# asset-tracker-v003.net
KiCad netlist of a schematic drawn in EAGLE
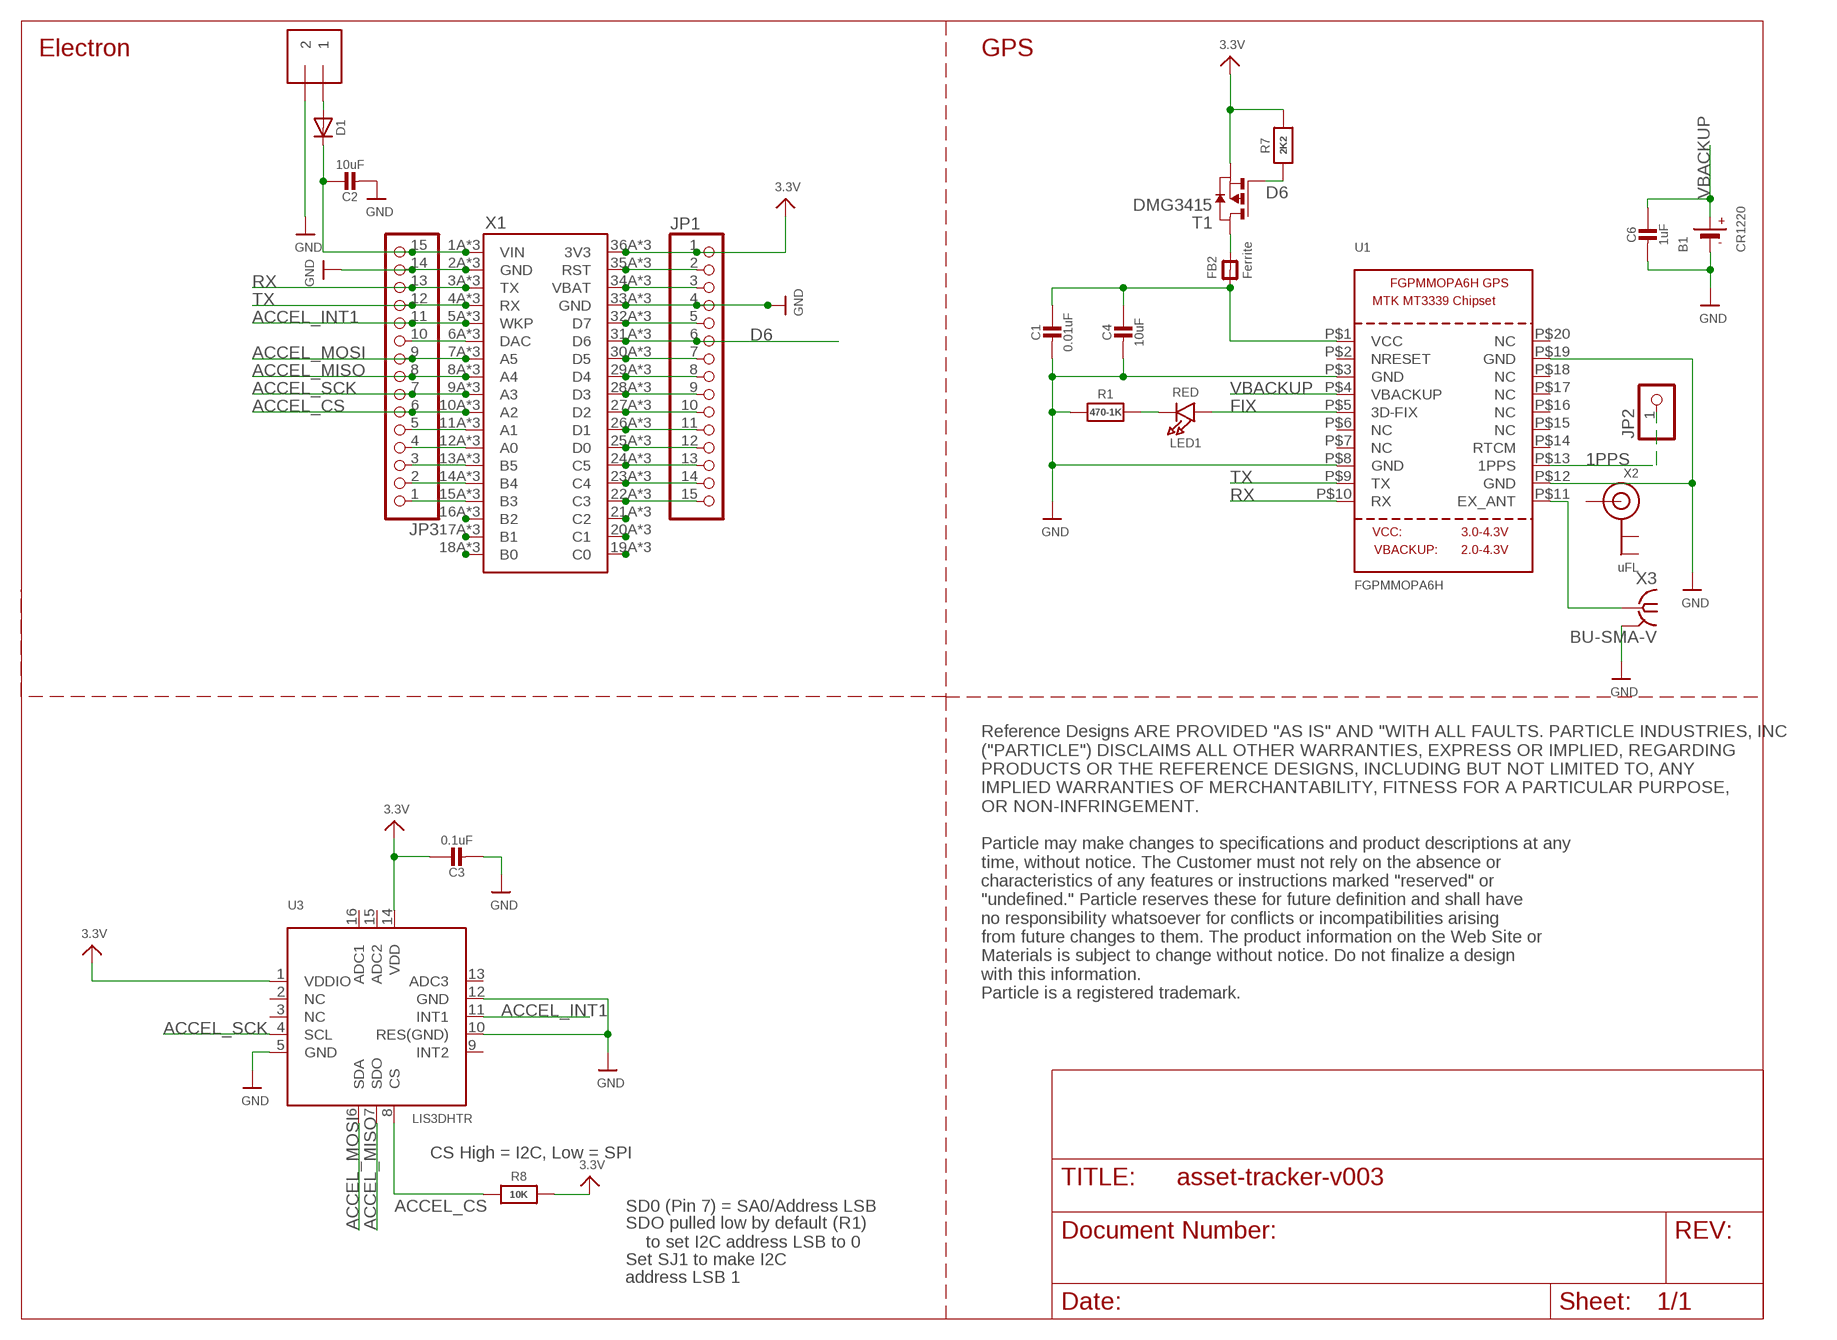
[diagram p0: schematic, sheet 1]

(export (version "E")
  (design (tool "Eeschema 10.0.6"))
  (components
    (comp (ref "B1")
      (value "CR1220")
      (footprint "eagle-import:CR1220")
      (libsource (lib "eagle-import") (part "BATTERYCR1220_SMT"))
    )
    (comp (ref "C1")
      (value "0.01uF")
      (footprint "eagle-import:0805-NO@1")
      (libsource (lib "eagle-import") (part "CAP_CERAMIC0805-NOOUTLINE"))
    )
    (comp (ref "C2")
      (value "10uF")
      (footprint "eagle-import:0805-NO@1")
      (libsource (lib "eagle-import") (part "CAP_CERAMIC0805-NOOUTLINE"))
    )
    (comp (ref "C3")
      (value "0.1uF")
      (footprint "eagle-import:0805_10MGAP")
      (libsource (lib "eagle-import") (part "CAP_CERAMIC0805_10MGAP"))
    )
    (comp (ref "C4")
      (value "10uF")
      (footprint "eagle-import:0805-NO@1")
      (libsource (lib "eagle-import") (part "CAP_CERAMIC0805-NOOUTLINE"))
    )
    (comp (ref "C6")
      (value "1uF")
      (footprint "eagle-import:0805-NO@1")
      (libsource (lib "eagle-import") (part "CAP_CERAMIC0805-NOOUTLINE"))
    )
    (comp (ref "D1")
      (value "DIODESMA")
      (footprint "eagle-import:SMADIODE")
      (libsource (lib "eagle-import") (part "DIODESMA"))
    )
    (comp (ref "FB2")
      (value "Ferrite")
      (footprint "eagle-import:0805-NO@1")
      (libsource (lib "eagle-import") (part "FERRITE-0805NO"))
    )
    (comp (ref "J1")
      (value "1X2-3.5MM")
      (footprint "eagle-import:1X2-3.5MM")
      (libsource (lib "eagle-import") (part "1X2-3.5MM"))
    )
    (comp (ref "JP1")
      (value "HEADER-1X15")
      (footprint "eagle-import:1X15_ROUND_70")
      (libsource (lib "eagle-import") (part "HEADER-1X15"))
    )
    (comp (ref "JP2")
      (value "HEADER-1X1ROUND")
      (footprint "eagle-import:1X01_ROUND")
      (libsource (lib "eagle-import") (part "HEADER-1X1ROUND"))
    )
    (comp (ref "JP3")
      (value "HEADER-1X15")
      (footprint "eagle-import:1X15_ROUND_70")
      (libsource (lib "eagle-import") (part "HEADER-1X15"))
    )
    (comp (ref "LED1")
      (value "RED")
      (footprint "eagle-import:CHIPLED_0805_NOOUTLINE")
      (libsource (lib "eagle-import") (part "LED0805_NOOUTLINE"))
    )
    (comp (ref "R1")
      (value "470-1K")
      (footprint "eagle-import:0805-NO")
      (libsource (lib "eagle-import") (part "RESISTOR0805_NOOUTLINE"))
    )
    (comp (ref "R7")
      (value "2K2")
      (footprint "eagle-import:0805-NO")
      (libsource (lib "eagle-import") (part "RESISTOR0805_NOOUTLINE"))
    )
    (comp (ref "R8")
      (value "10K")
      (footprint "eagle-import:0805-NO")
      (libsource (lib "eagle-import") (part "RESISTOR0805_NOOUTLINE"))
    )
    (comp (ref "T1")
      (value "DMG3415")
      (footprint "eagle-import:SOT-23")
      (libsource (lib "eagle-import") (part "PMOSSOT23"))
    )
    (comp (ref "U1")
      (value "FGPMMOPA6H")
      (footprint "eagle-import:FGPMMOPA6H")
      (libsource (lib "eagle-import") (part "GPS_FGPMMOPA6H"))
    )
    (comp (ref "U3")
      (value "LIS3DHTR")
      (footprint "eagle-import:LGA16_3X3MM")
      (libsource (lib "eagle-import") (part "ACCEL_LIS3DHTR"))
    )
    (comp (ref "X1")
      (value "ELECTRON")
      (footprint "eagle-import:ELECTRON_SMT")
      (libsource (lib "eagle-import") (part "ELECTRON_SMT"))
    )
    (comp (ref "X2")
      (value "uFL")
      (footprint "eagle-import:U.FL")
      (libsource (lib "eagle-import") (part "ANTENNA_U.FL"))
    )
    (comp (ref "X3")
      (value "BU-SMA-V")
      (footprint "eagle-import:BU-SMA-V")
      (libsource (lib "eagle-import") (part "BU-SMA-V"))
    )
  )
  (nets
    (net (code "1") (name "/1PPS") (class "Default")
      (node (ref "JP2") (pin "1") (pinfunction "1_1") (pintype "passive"))
      (node (ref "U1") (pin "P$13") (pinfunction "1PPS_P$13") (pintype "bidirectional"))
    )
    (net (code "2") (name "/ACCEL_CS") (class "Default")
      (node (ref "JP3") (pin "6") (pinfunction "6_6") (pintype "passive"))
      (node (ref "R8") (pin "1") (pinfunction "1_1") (pintype "passive"))
      (node (ref "U3") (pin "8") (pinfunction "CS_8") (pintype "input"))
      (node (ref "X1") (pin "10A") (pinfunction "A2_10A") (pintype "bidirectional"))
      (node (ref "X1") (pin "10B") (pinfunction "A2_10B") (pintype "bidirectional"))
      (node (ref "X1") (pin "10C") (pinfunction "A2_10C") (pintype "bidirectional"))
    )
    (net (code "3") (name "/ACCEL_INT1") (class "Default")
      (node (ref "JP3") (pin "11") (pinfunction "11_11") (pintype "passive"))
      (node (ref "U3") (pin "11") (pinfunction "INT1_11") (pintype "output"))
      (node (ref "X1") (pin "5A") (pinfunction "WKP_5A") (pintype "bidirectional"))
      (node (ref "X1") (pin "5B") (pinfunction "WKP_5B") (pintype "bidirectional"))
      (node (ref "X1") (pin "5C") (pinfunction "WKP_5C") (pintype "bidirectional"))
    )
    (net (code "4") (name "/ACCEL_MISO") (class "Default")
      (node (ref "JP3") (pin "8") (pinfunction "8_8") (pintype "passive"))
      (node (ref "U3") (pin "7") (pinfunction "SDO_7") (pintype "bidirectional"))
      (node (ref "X1") (pin "8A") (pinfunction "A4_8A") (pintype "bidirectional"))
      (node (ref "X1") (pin "8B") (pinfunction "A4_8B") (pintype "bidirectional"))
      (node (ref "X1") (pin "8C") (pinfunction "A4_8C") (pintype "bidirectional"))
    )
    (net (code "5") (name "/ACCEL_MOSI") (class "Default")
      (node (ref "JP3") (pin "9") (pinfunction "9_9") (pintype "passive"))
      (node (ref "U3") (pin "6") (pinfunction "SDA_6") (pintype "bidirectional"))
      (node (ref "X1") (pin "7A") (pinfunction "A5_7A") (pintype "bidirectional"))
      (node (ref "X1") (pin "7B") (pinfunction "A5_7B") (pintype "bidirectional"))
      (node (ref "X1") (pin "7C") (pinfunction "A5_7C") (pintype "bidirectional"))
    )
    (net (code "6") (name "/ACCEL_SCK") (class "Default")
      (node (ref "JP3") (pin "7") (pinfunction "7_7") (pintype "passive"))
      (node (ref "U3") (pin "4") (pinfunction "SCL_4") (pintype "bidirectional"))
      (node (ref "X1") (pin "9A") (pinfunction "A3_9A") (pintype "bidirectional"))
      (node (ref "X1") (pin "9B") (pinfunction "A3_9B") (pintype "bidirectional"))
      (node (ref "X1") (pin "9C") (pinfunction "A3_9C") (pintype "bidirectional"))
    )
    (net (code "7") (name "/D6") (class "Default")
      (node (ref "JP1") (pin "6") (pinfunction "6_6") (pintype "passive"))
      (node (ref "R7") (pin "1") (pinfunction "1_1") (pintype "passive"))
      (node (ref "T1") (pin "3") (pinfunction "G_3") (pintype "passive"))
      (node (ref "X1") (pin "31A") (pinfunction "D6_31A") (pintype "bidirectional"))
      (node (ref "X1") (pin "31B") (pinfunction "D6_31B") (pintype "bidirectional"))
      (node (ref "X1") (pin "31C") (pinfunction "D6_31C") (pintype "bidirectional"))
    )
    (net (code "8") (name "/FIX") (class "Default")
      (node (ref "LED1") (pin "A") (pinfunction "A_A") (pintype "passive"))
      (node (ref "U1") (pin "P$5") (pinfunction "3D-FIX_P$5") (pintype "bidirectional"))
    )
    (net (code "9") (name "/RX") (class "Default")
      (node (ref "JP3") (pin "13") (pinfunction "13_13") (pintype "passive"))
      (node (ref "U1") (pin "P$10") (pinfunction "RX_P$10") (pintype "bidirectional"))
      (node (ref "X1") (pin "3A") (pinfunction "TX_3A") (pintype "bidirectional"))
      (node (ref "X1") (pin "3B") (pinfunction "TX_3B") (pintype "bidirectional"))
      (node (ref "X1") (pin "3C") (pinfunction "TX_3C") (pintype "bidirectional"))
    )
    (net (code "10") (name "/TX") (class "Default")
      (node (ref "JP3") (pin "12") (pinfunction "12_12") (pintype "passive"))
      (node (ref "U1") (pin "P$9") (pinfunction "TX_P$9") (pintype "bidirectional"))
      (node (ref "X1") (pin "4A") (pinfunction "RX_4A") (pintype "bidirectional"))
      (node (ref "X1") (pin "4B") (pinfunction "RX_4B") (pintype "bidirectional"))
      (node (ref "X1") (pin "4C") (pinfunction "RX_4C") (pintype "bidirectional"))
    )
    (net (code "11") (name "/VBACKUP") (class "Default")
      (node (ref "B1") (pin "+$1") (pinfunction "+_+$1") (pintype "passive"))
      (node (ref "C6") (pin "1") (pinfunction "1_1") (pintype "passive"))
      (node (ref "U1") (pin "P$4") (pinfunction "VBACKUP_P$4") (pintype "bidirectional"))
    )
    (net (code "12") (name "3.3V") (class "Default")
      (node (ref "C3") (pin "1") (pinfunction "1_1") (pintype "passive"))
      (node (ref "JP1") (pin "1") (pinfunction "1_1") (pintype "passive"))
      (node (ref "R7") (pin "2") (pinfunction "2_2") (pintype "passive"))
      (node (ref "R8") (pin "2") (pinfunction "2_2") (pintype "passive"))
      (node (ref "T1") (pin "2") (pinfunction "S_2") (pintype "passive"))
      (node (ref "U3") (pin "1") (pinfunction "VDDIO_1") (pintype "power_in"))
      (node (ref "U3") (pin "14") (pinfunction "VDD_14") (pintype "power_in"))
      (node (ref "X1") (pin "36A") (pinfunction "3V3_36A") (pintype "power_in"))
      (node (ref "X1") (pin "36B") (pinfunction "3V3_36B") (pintype "power_in"))
      (node (ref "X1") (pin "36C") (pinfunction "3V3_36C") (pintype "power_in"))
    )
    (net (code "13") (name "GND") (class "Default")
      (node (ref "B1") (pin "-") (pinfunction "-_-") (pintype "passive"))
      (node (ref "C1") (pin "2") (pinfunction "2_2") (pintype "passive"))
      (node (ref "C2") (pin "2") (pinfunction "2_2") (pintype "passive"))
      (node (ref "C3") (pin "2") (pinfunction "2_2") (pintype "passive"))
      (node (ref "C4") (pin "2") (pinfunction "2_2") (pintype "passive"))
      (node (ref "C6") (pin "2") (pinfunction "2_2") (pintype "passive"))
      (node (ref "J1") (pin "2") (pinfunction "2_2") (pintype "passive"))
      (node (ref "JP1") (pin "4") (pinfunction "4_4") (pintype "passive"))
      (node (ref "JP3") (pin "14") (pinfunction "14_14") (pintype "passive"))
      (node (ref "R1") (pin "1") (pinfunction "1_1") (pintype "passive"))
      (node (ref "U1") (pin "P$12") (pinfunction "GND_P$12") (pintype "bidirectional"))
      (node (ref "U1") (pin "P$19") (pinfunction "GND_P$19") (pintype "bidirectional"))
      (node (ref "U1") (pin "P$3") (pinfunction "GND_P$3") (pintype "bidirectional"))
      (node (ref "U1") (pin "P$8") (pinfunction "GND_P$8") (pintype "bidirectional"))
      (node (ref "U3") (pin "10") (pinfunction "RES(GND)_10") (pintype "bidirectional"))
      (node (ref "U3") (pin "12") (pinfunction "GND_12") (pintype "power_in"))
      (node (ref "U3") (pin "5") (pinfunction "GND_5") (pintype "power_in"))
      (node (ref "X1") (pin "2A") (pinfunction "GND_2A") (pintype "power_in"))
      (node (ref "X1") (pin "2B") (pinfunction "GND_2B") (pintype "power_in"))
      (node (ref "X1") (pin "2C") (pinfunction "GND_2C") (pintype "power_in"))
      (node (ref "X1") (pin "33A") (pinfunction "GND_33A") (pintype "power_in"))
      (node (ref "X1") (pin "33B") (pinfunction "GND_33B") (pintype "power_in"))
      (node (ref "X1") (pin "33C") (pinfunction "GND_33C") (pintype "power_in"))
      (node (ref "X3") (pin "2") (pinfunction "2_2") (pintype "passive"))
      (node (ref "X3") (pin "3") (pinfunction "2_3") (pintype "passive"))
      (node (ref "X3") (pin "4") (pinfunction "2_4") (pintype "passive"))
      (node (ref "X3") (pin "5") (pinfunction "2_5") (pintype "passive"))
    )
    (net (code "14") (name "Net-(C2-Pad1)") (class "Default")
      (node (ref "C2") (pin "1") (pinfunction "1_1") (pintype "passive"))
      (node (ref "D1") (pin "C") (pinfunction "C_C") (pintype "passive"))
      (node (ref "JP3") (pin "15") (pinfunction "15_15") (pintype "passive"))
      (node (ref "X1") (pin "1A") (pinfunction "VIN_1A") (pintype "power_in"))
      (node (ref "X1") (pin "1B") (pinfunction "VIN_1B") (pintype "power_in"))
      (node (ref "X1") (pin "1C") (pinfunction "VIN_1C") (pintype "power_in"))
    )
    (net (code "15") (name "Net-(D1-PadA)") (class "Default")
      (node (ref "D1") (pin "A") (pinfunction "A_A") (pintype "passive"))
      (node (ref "J1") (pin "1") (pinfunction "1_1") (pintype "passive"))
    )
    (net (code "16") (name "Net-(FB2-P$1)") (class "Default")
      (node (ref "C1") (pin "1") (pinfunction "1_1") (pintype "passive"))
      (node (ref "C4") (pin "1") (pinfunction "1_1") (pintype "passive"))
      (node (ref "FB2") (pin "1") (pinfunction "P$1_1") (pintype "passive"))
      (node (ref "U1") (pin "P$1") (pinfunction "VCC_P$1") (pintype "bidirectional"))
    )
    (net (code "17") (name "Net-(FB2-P$2)") (class "Default")
      (node (ref "FB2") (pin "2") (pinfunction "P$2_2") (pintype "passive"))
      (node (ref "T1") (pin "1") (pinfunction "D_1") (pintype "passive"))
    )
    (net (code "18") (name "Net-(JP1-Pad2)") (class "Default")
      (node (ref "JP1") (pin "2") (pinfunction "2_2") (pintype "passive"))
      (node (ref "X1") (pin "35A") (pinfunction "RST_35A") (pintype "bidirectional"))
      (node (ref "X1") (pin "35B") (pinfunction "RST_35B") (pintype "bidirectional"))
      (node (ref "X1") (pin "35C") (pinfunction "RST_35C") (pintype "bidirectional"))
    )
    (net (code "19") (name "Net-(JP1-Pad3)") (class "Default")
      (node (ref "JP1") (pin "3") (pinfunction "3_3") (pintype "passive"))
      (node (ref "X1") (pin "34A") (pinfunction "VBAT_34A") (pintype "passive"))
      (node (ref "X1") (pin "34B") (pinfunction "VBAT_34B") (pintype "passive"))
      (node (ref "X1") (pin "34C") (pinfunction "VBAT_34C") (pintype "passive"))
    )
    (net (code "20") (name "Net-(JP1-Pad5)") (class "Default")
      (node (ref "JP1") (pin "5") (pinfunction "5_5") (pintype "passive"))
      (node (ref "X1") (pin "32A") (pinfunction "D7_32A") (pintype "bidirectional"))
      (node (ref "X1") (pin "32B") (pinfunction "D7_32B") (pintype "bidirectional"))
      (node (ref "X1") (pin "32C") (pinfunction "D7_32C") (pintype "bidirectional"))
    )
    (net (code "21") (name "Net-(JP1-Pad7)") (class "Default")
      (node (ref "JP1") (pin "7") (pinfunction "7_7") (pintype "passive"))
      (node (ref "X1") (pin "30A") (pinfunction "D5_30A") (pintype "bidirectional"))
      (node (ref "X1") (pin "30B") (pinfunction "D5_30B") (pintype "bidirectional"))
      (node (ref "X1") (pin "30C") (pinfunction "D5_30C") (pintype "bidirectional"))
    )
    (net (code "22") (name "Net-(JP1-Pad8)") (class "Default")
      (node (ref "JP1") (pin "8") (pinfunction "8_8") (pintype "passive"))
      (node (ref "X1") (pin "29A") (pinfunction "D4_29A") (pintype "bidirectional"))
      (node (ref "X1") (pin "29B") (pinfunction "D4_29B") (pintype "bidirectional"))
      (node (ref "X1") (pin "29C") (pinfunction "D4_29C") (pintype "bidirectional"))
    )
    (net (code "23") (name "Net-(JP1-Pad9)") (class "Default")
      (node (ref "JP1") (pin "9") (pinfunction "9_9") (pintype "passive"))
      (node (ref "X1") (pin "28A") (pinfunction "D3_28A") (pintype "bidirectional"))
      (node (ref "X1") (pin "28B") (pinfunction "D3_28B") (pintype "bidirectional"))
      (node (ref "X1") (pin "28C") (pinfunction "D3_28C") (pintype "bidirectional"))
    )
    (net (code "24") (name "Net-(JP1-Pad10)") (class "Default")
      (node (ref "JP1") (pin "10") (pinfunction "10_10") (pintype "passive"))
      (node (ref "X1") (pin "27A") (pinfunction "D2_27A") (pintype "bidirectional"))
      (node (ref "X1") (pin "27B") (pinfunction "D2_27B") (pintype "bidirectional"))
      (node (ref "X1") (pin "27C") (pinfunction "D2_27C") (pintype "bidirectional"))
    )
    (net (code "25") (name "Net-(JP1-Pad11)") (class "Default")
      (node (ref "JP1") (pin "11") (pinfunction "11_11") (pintype "passive"))
      (node (ref "X1") (pin "26A") (pinfunction "D1_26A") (pintype "bidirectional"))
      (node (ref "X1") (pin "26B") (pinfunction "D1_26B") (pintype "bidirectional"))
      (node (ref "X1") (pin "26C") (pinfunction "D1_26C") (pintype "bidirectional"))
    )
    (net (code "26") (name "Net-(JP1-Pad12)") (class "Default")
      (node (ref "JP1") (pin "12") (pinfunction "12_12") (pintype "passive"))
      (node (ref "X1") (pin "25A") (pinfunction "D0_25A") (pintype "bidirectional"))
      (node (ref "X1") (pin "25B") (pinfunction "D0_25B") (pintype "bidirectional"))
      (node (ref "X1") (pin "25C") (pinfunction "D0_25C") (pintype "bidirectional"))
    )
    (net (code "27") (name "Net-(JP1-Pad13)") (class "Default")
      (node (ref "JP1") (pin "13") (pinfunction "13_13") (pintype "passive"))
      (node (ref "X1") (pin "24A") (pinfunction "C5_24A") (pintype "bidirectional"))
      (node (ref "X1") (pin "24B") (pinfunction "C5_24B") (pintype "bidirectional"))
      (node (ref "X1") (pin "24C") (pinfunction "C5_24C") (pintype "bidirectional"))
    )
    (net (code "28") (name "Net-(JP1-Pad14)") (class "Default")
      (node (ref "JP1") (pin "14") (pinfunction "14_14") (pintype "passive"))
      (node (ref "X1") (pin "23A") (pinfunction "C4_23A") (pintype "bidirectional"))
      (node (ref "X1") (pin "23B") (pinfunction "C4_23B") (pintype "bidirectional"))
      (node (ref "X1") (pin "23C") (pinfunction "C4_23C") (pintype "bidirectional"))
    )
    (net (code "29") (name "Net-(JP1-Pad15)") (class "Default")
      (node (ref "JP1") (pin "15") (pinfunction "15_15") (pintype "passive"))
      (node (ref "X1") (pin "22A") (pinfunction "C3_22A") (pintype "bidirectional"))
      (node (ref "X1") (pin "22B") (pinfunction "C3_22B") (pintype "bidirectional"))
      (node (ref "X1") (pin "22C") (pinfunction "C3_22C") (pintype "bidirectional"))
    )
    (net (code "30") (name "Net-(JP3-Pad1)") (class "Default")
      (node (ref "JP3") (pin "1") (pinfunction "1_1") (pintype "passive"))
      (node (ref "X1") (pin "15A") (pinfunction "B3_15A") (pintype "bidirectional"))
      (node (ref "X1") (pin "15B") (pinfunction "B3_15B") (pintype "bidirectional"))
      (node (ref "X1") (pin "15C") (pinfunction "B3_15C") (pintype "bidirectional"))
    )
    (net (code "31") (name "Net-(JP3-Pad2)") (class "Default")
      (node (ref "JP3") (pin "2") (pinfunction "2_2") (pintype "passive"))
      (node (ref "X1") (pin "14A") (pinfunction "B4_14A") (pintype "bidirectional"))
      (node (ref "X1") (pin "14B") (pinfunction "B4_14B") (pintype "bidirectional"))
      (node (ref "X1") (pin "14C") (pinfunction "B4_14C") (pintype "bidirectional"))
    )
    (net (code "32") (name "Net-(JP3-Pad3)") (class "Default")
      (node (ref "JP3") (pin "3") (pinfunction "3_3") (pintype "passive"))
      (node (ref "X1") (pin "13A") (pinfunction "B5_13A") (pintype "bidirectional"))
      (node (ref "X1") (pin "13B") (pinfunction "B5_13B") (pintype "bidirectional"))
      (node (ref "X1") (pin "13C") (pinfunction "B5_13C") (pintype "bidirectional"))
    )
    (net (code "33") (name "Net-(JP3-Pad4)") (class "Default")
      (node (ref "JP3") (pin "4") (pinfunction "4_4") (pintype "passive"))
      (node (ref "X1") (pin "12A") (pinfunction "A0_12A") (pintype "bidirectional"))
      (node (ref "X1") (pin "12B") (pinfunction "A0_12B") (pintype "bidirectional"))
      (node (ref "X1") (pin "12C") (pinfunction "A0_12C") (pintype "bidirectional"))
    )
    (net (code "34") (name "Net-(JP3-Pad5)") (class "Default")
      (node (ref "JP3") (pin "5") (pinfunction "5_5") (pintype "passive"))
      (node (ref "X1") (pin "11A") (pinfunction "A1_11A") (pintype "bidirectional"))
      (node (ref "X1") (pin "11B") (pinfunction "A1_11B") (pintype "bidirectional"))
      (node (ref "X1") (pin "11C") (pinfunction "A1_11C") (pintype "bidirectional"))
    )
    (net (code "35") (name "Net-(JP3-Pad10)") (class "Default")
      (node (ref "JP3") (pin "10") (pinfunction "10_10") (pintype "passive"))
      (node (ref "X1") (pin "6A") (pinfunction "DAC_6A") (pintype "bidirectional"))
      (node (ref "X1") (pin "6B") (pinfunction "DAC_6B") (pintype "bidirectional"))
      (node (ref "X1") (pin "6C") (pinfunction "DAC_6C") (pintype "bidirectional"))
    )
    (net (code "36") (name "Net-(LED1-PadC)") (class "Default")
      (node (ref "LED1") (pin "C") (pinfunction "C_C") (pintype "passive"))
      (node (ref "R1") (pin "2") (pinfunction "2_2") (pintype "passive"))
    )
    (net (code "37") (name "Net-(U1-EX_ANT)") (class "Default")
      (node (ref "U1") (pin "P$11") (pinfunction "EX_ANT_P$11") (pintype "bidirectional"))
      (node (ref "X3") (pin "1") (pinfunction "1_1") (pintype "passive"))
    )
    (net (code "38") (name "Net-(X1-B0-Pad18A)") (class "Default")
      (node (ref "X1") (pin "18A") (pinfunction "B0_18A") (pintype "bidirectional"))
      (node (ref "X1") (pin "18B") (pinfunction "B0_18B") (pintype "bidirectional"))
      (node (ref "X1") (pin "18C") (pinfunction "B0_18C") (pintype "bidirectional"))
    )
    (net (code "39") (name "Net-(X1-B1-Pad17A)") (class "Default")
      (node (ref "X1") (pin "17A") (pinfunction "B1_17A") (pintype "bidirectional"))
      (node (ref "X1") (pin "17B") (pinfunction "B1_17B") (pintype "bidirectional"))
      (node (ref "X1") (pin "17C") (pinfunction "B1_17C") (pintype "bidirectional"))
    )
    (net (code "40") (name "Net-(X1-B2-Pad16A)") (class "Default")
      (node (ref "X1") (pin "16A") (pinfunction "B2_16A") (pintype "bidirectional"))
      (node (ref "X1") (pin "16B") (pinfunction "B2_16B") (pintype "bidirectional"))
      (node (ref "X1") (pin "16C") (pinfunction "B2_16C") (pintype "bidirectional"))
    )
    (net (code "41") (name "Net-(X1-C0-Pad19A)") (class "Default")
      (node (ref "X1") (pin "19A") (pinfunction "C0_19A") (pintype "bidirectional"))
      (node (ref "X1") (pin "19B") (pinfunction "C0_19B") (pintype "bidirectional"))
      (node (ref "X1") (pin "19C") (pinfunction "C0_19C") (pintype "bidirectional"))
    )
    (net (code "42") (name "Net-(X1-C1-Pad20A)") (class "Default")
      (node (ref "X1") (pin "20A") (pinfunction "C1_20A") (pintype "bidirectional"))
      (node (ref "X1") (pin "20B") (pinfunction "C1_20B") (pintype "bidirectional"))
      (node (ref "X1") (pin "20C") (pinfunction "C1_20C") (pintype "bidirectional"))
    )
    (net (code "43") (name "Net-(X1-C2-Pad21A)") (class "Default")
      (node (ref "X1") (pin "21A") (pinfunction "C2_21A") (pintype "bidirectional"))
      (node (ref "X1") (pin "21B") (pinfunction "C2_21B") (pintype "bidirectional"))
      (node (ref "X1") (pin "21C") (pinfunction "C2_21C") (pintype "bidirectional"))
    )
    (net (code "44") (name "unconnected-(U1-NC-PadP$6)") (class "Default")
      (node (ref "U1") (pin "P$6") (pinfunction "NC_P$6") (pintype "bidirectional"))
    )
    (net (code "45") (name "unconnected-(U1-NC-PadP$7)") (class "Default")
      (node (ref "U1") (pin "P$7") (pinfunction "NC_P$7") (pintype "bidirectional"))
    )
    (net (code "46") (name "unconnected-(U1-NC-PadP$15)") (class "Default")
      (node (ref "U1") (pin "P$15") (pinfunction "NC_P$15") (pintype "bidirectional"))
    )
    (net (code "47") (name "unconnected-(U1-NC-PadP$16)") (class "Default")
      (node (ref "U1") (pin "P$16") (pinfunction "NC_P$16") (pintype "bidirectional"))
    )
    (net (code "48") (name "unconnected-(U1-NC-PadP$17)") (class "Default")
      (node (ref "U1") (pin "P$17") (pinfunction "NC_P$17") (pintype "bidirectional"))
    )
    (net (code "49") (name "unconnected-(U1-NC-PadP$18)") (class "Default")
      (node (ref "U1") (pin "P$18") (pinfunction "NC_P$18") (pintype "bidirectional"))
    )
    (net (code "50") (name "unconnected-(U1-NC-PadP$20)") (class "Default")
      (node (ref "U1") (pin "P$20") (pinfunction "NC_P$20") (pintype "bidirectional"))
    )
    (net (code "51") (name "unconnected-(U1-NRESET-PadP$2)") (class "Default")
      (node (ref "U1") (pin "P$2") (pinfunction "NRESET_P$2") (pintype "bidirectional"))
    )
    (net (code "52") (name "unconnected-(U1-RTCM-PadP$14)") (class "Default")
      (node (ref "U1") (pin "P$14") (pinfunction "RTCM_P$14") (pintype "bidirectional"))
    )
    (net (code "53") (name "unconnected-(U3-ADC1-Pad16)") (class "Default")
      (node (ref "U3") (pin "16") (pinfunction "ADC1_16") (pintype "input"))
    )
    (net (code "54") (name "unconnected-(U3-ADC2-Pad15)") (class "Default")
      (node (ref "U3") (pin "15") (pinfunction "ADC2_15") (pintype "input"))
    )
    (net (code "55") (name "unconnected-(U3-ADC3-Pad13)") (class "Default")
      (node (ref "U3") (pin "13") (pinfunction "ADC3_13") (pintype "input"))
    )
    (net (code "56") (name "unconnected-(U3-INT2-Pad9)") (class "Default")
      (node (ref "U3") (pin "9") (pinfunction "INT2_9") (pintype "output"))
    )
    (net (code "57") (name "unconnected-(U3-NC-Pad2)") (class "Default")
      (node (ref "U3") (pin "2") (pinfunction "NC_2") (pintype "no_connect"))
    )
    (net (code "58") (name "unconnected-(U3-NC-Pad3)") (class "Default")
      (node (ref "U3") (pin "3") (pinfunction "NC_3") (pintype "no_connect"))
    )
    (net (code "59") (name "unconnected-(X2-GND-Pad1)") (class "Default")
      (node (ref "X2") (pin "1") (pinfunction "GND_1") (pintype "passive"))
    )
    (net (code "60") (name "unconnected-(X2-GND-Pad2)") (class "Default")
      (node (ref "X2") (pin "2") (pinfunction "GND_2") (pintype "passive"))
    )
    (net (code "61") (name "unconnected-(X2-SIGNAL-Pad3)") (class "Default")
      (node (ref "X2") (pin "3") (pinfunction "SIGNAL_3") (pintype "passive"))
    )
  )
)
